# SensorCircuits2.net
KiCad netlist of a schematic drawn in EAGLE
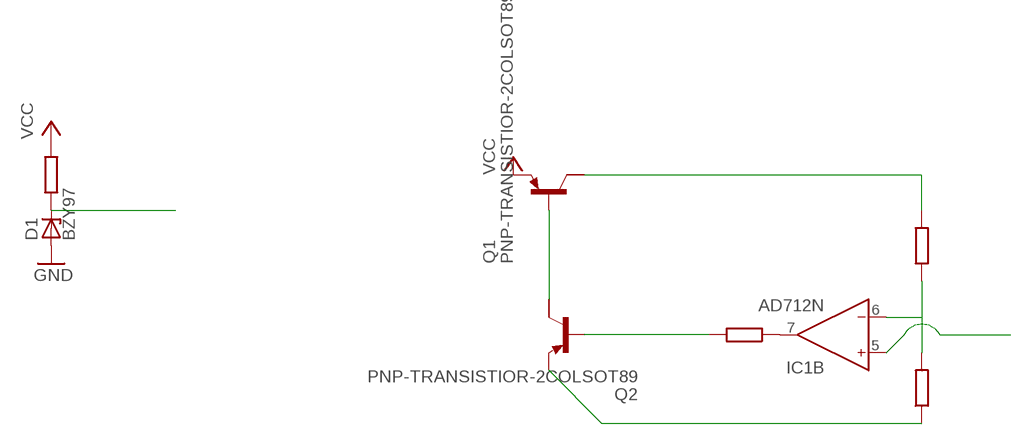
[diagram p0: schematic, sheet 1]

(export (version "E")
  (design (tool "Eeschema 10.0.6"))
  (components
    (comp (ref "D1")
      (value "BZY97")
      (footprint "eagle-import:F126Z12")
      (libsource (lib "eagle-import") (part "BZY97"))
    )
    (comp (ref "IC1")
      (value "AD712N")
      (footprint "eagle-import:DIL08")
      (fields (field (name "MF") "ALTERA CORPORATION") (field (name "MPN") "AD712JNZ"))
      (libsource (lib "eagle-import") (part "AD712N"))
    )
    (comp (ref "Q1")
      (value "PNP-TRANSISTIOR-2COLSOT89")
      (footprint "eagle-import:SOT89")
      (libsource (lib "eagle-import") (part "PNP-TRANSISTIOR-2COLSOT89"))
    )
    (comp (ref "Q2")
      (value "PNP-TRANSISTIOR-2COLSOT89")
      (footprint "eagle-import:SOT89")
      (libsource (lib "eagle-import") (part "PNP-TRANSISTIOR-2COLSOT89"))
    )
  )
  (nets
    (net (code "1") (name "GND") (class "Default")
      (node (ref "D1") (pin "A") (pinfunction "A_A") (pintype "passive"))
    )
    (net (code "2") (name "Net-(Q1-B)") (class "Default")
      (node (ref "Q1") (pin "1") (pinfunction "B_1") (pintype "passive"))
      (node (ref "Q2") (pin "2") (pinfunction "C_2") (pintype "passive"))
    )
    (net (code "3") (name "VCC") (class "Default")
      (node (ref "Q1") (pin "3") (pinfunction "E_3") (pintype "passive"))
    )
    (net (code "4") (name "unconnected-(D1-PadC)") (class "Default")
      (node (ref "D1") (pin "C") (pinfunction "C_C") (pintype "passive"))
    )
    (net (code "5") (name "unconnected-(IC1B-IN+-Pad5)") (class "Default")
      (node (ref "IC1") (pin "5") (pinfunction "IN+_5") (pintype "input"))
    )
    (net (code "6") (name "unconnected-(IC1B-IN--Pad6)") (class "Default")
      (node (ref "IC1") (pin "6") (pinfunction "IN-_6") (pintype "input"))
    )
    (net (code "7") (name "unconnected-(IC1B-OUT-Pad7)") (class "Default")
      (node (ref "IC1") (pin "7") (pinfunction "OUT_7") (pintype "output"))
    )
    (net (code "8") (name "unconnected-(Q1-C-Pad2)") (class "Default")
      (node (ref "Q1") (pin "2") (pinfunction "C_2") (pintype "passive"))
    )
    (net (code "9") (name "unconnected-(Q1-C{slash}-Pad2@1)") (class "Default")
      (node (ref "Q1") (pin "2@1") (pinfunction "C/_2@1") (pintype "passive"))
    )
    (net (code "10") (name "unconnected-(Q2-B-Pad1)") (class "Default")
      (node (ref "Q2") (pin "1") (pinfunction "B_1") (pintype "passive"))
    )
    (net (code "11") (name "unconnected-(Q2-C{slash}-Pad2@1)") (class "Default")
      (node (ref "Q2") (pin "2@1") (pinfunction "C/_2@1") (pintype "passive"))
    )
    (net (code "12") (name "unconnected-(Q2-E-Pad3)") (class "Default")
      (node (ref "Q2") (pin "3") (pinfunction "E_3") (pintype "passive"))
    )
  )
)
